# ESP32_DSP.net
KiCad netlist of a schematic drawn in EAGLE
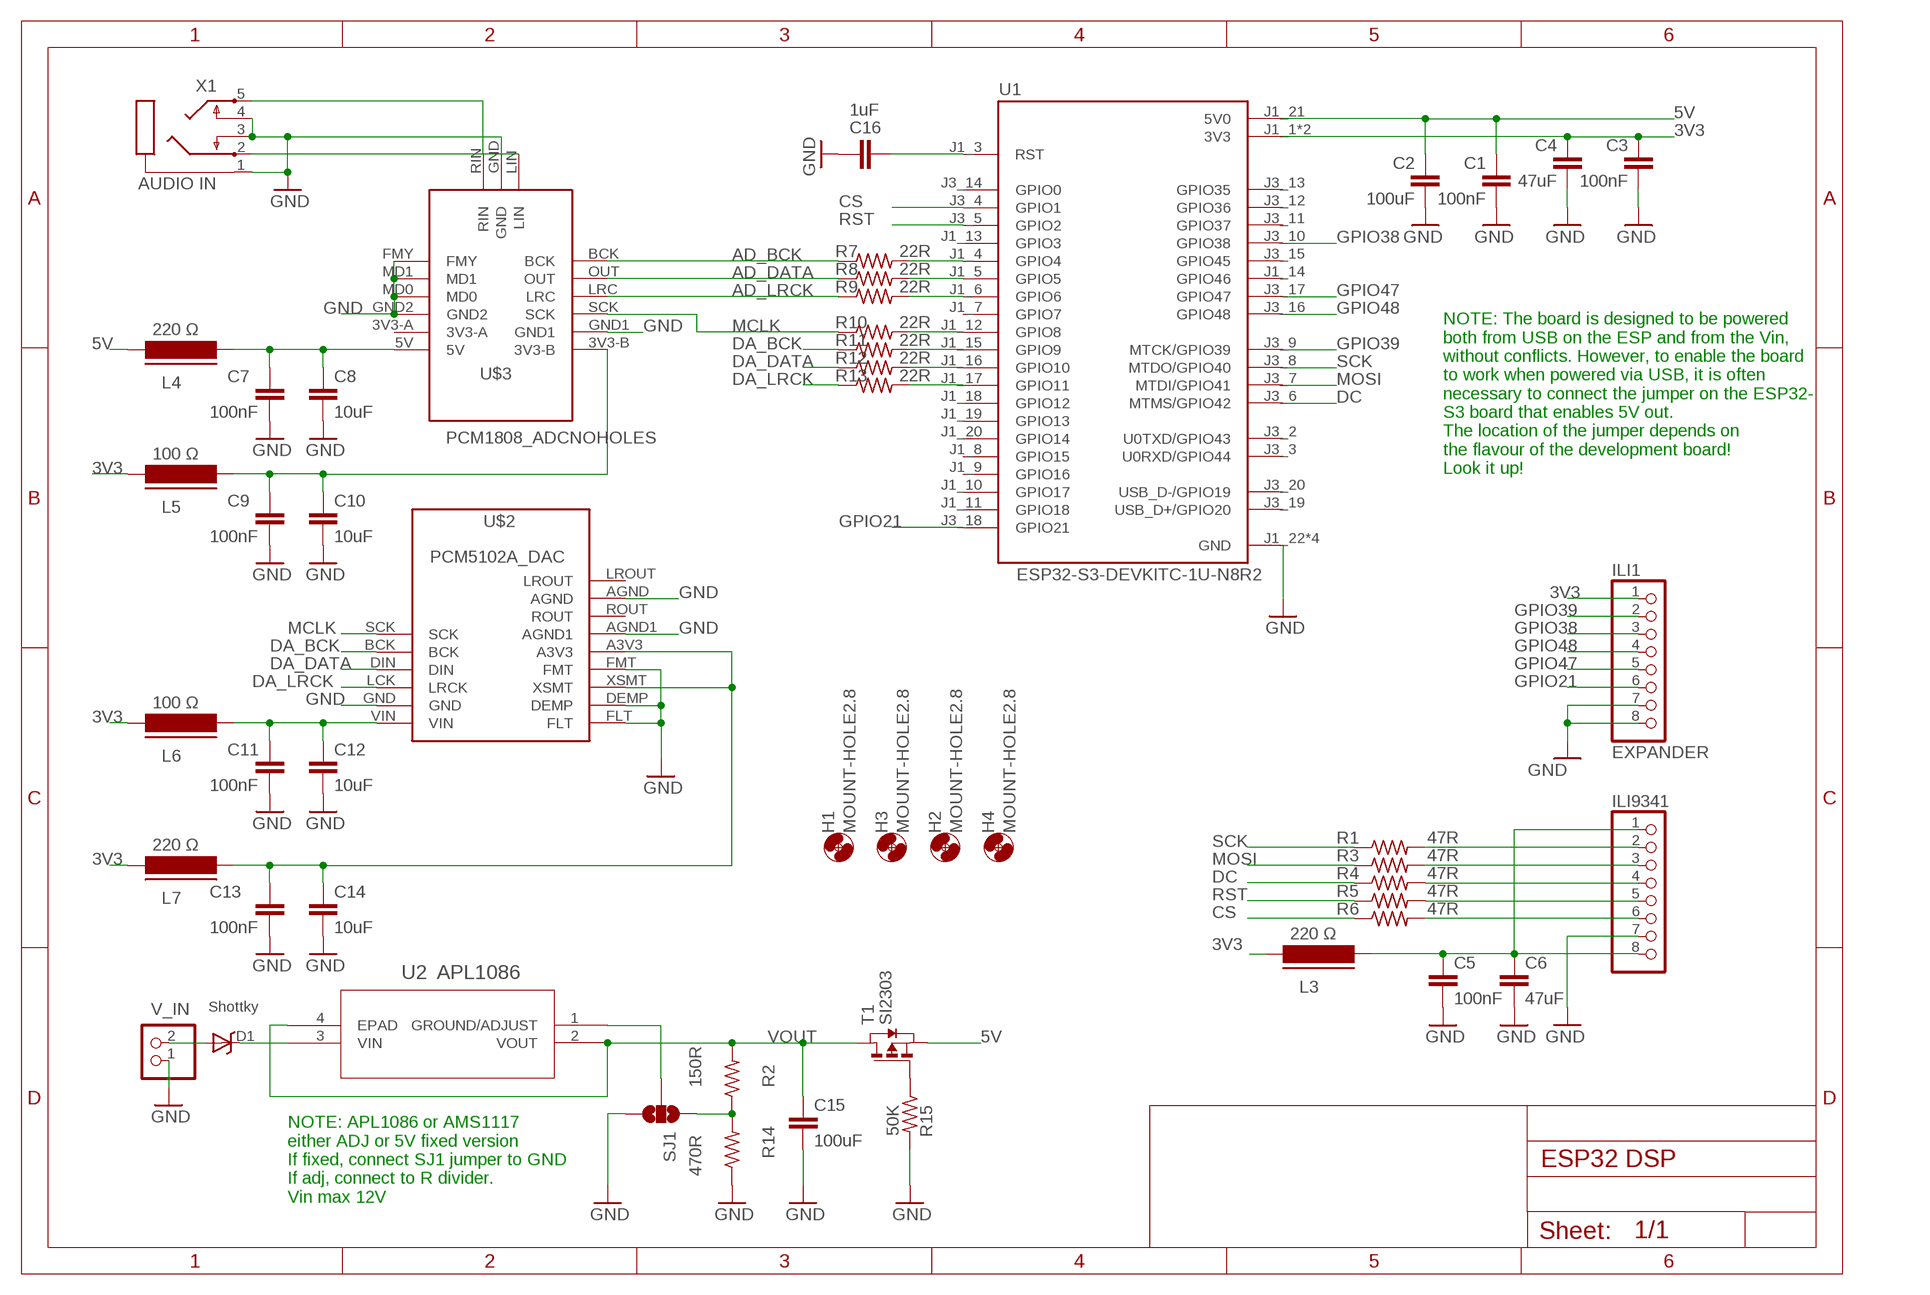
[diagram p0: schematic, sheet 1]

(export (version "E")
  (design (tool "Eeschema 10.0.6"))
  (components
    (comp (ref "C1")
      (value "100nF")
      (footprint "eagle-import:C0805")
      (libsource (lib "eagle-import") (part "C-EUC0805"))
    )
    (comp (ref "C2")
      (value "100uF")
      (footprint "eagle-import:C0805")
      (libsource (lib "eagle-import") (part "C-EUC0805"))
    )
    (comp (ref "C3")
      (value "100nF")
      (footprint "eagle-import:C0805")
      (libsource (lib "eagle-import") (part "C-EUC0805"))
    )
    (comp (ref "C4")
      (value "47uF")
      (footprint "eagle-import:C0805")
      (libsource (lib "eagle-import") (part "C-EUC0805"))
    )
    (comp (ref "C5")
      (value "100nF")
      (footprint "eagle-import:C0805")
      (libsource (lib "eagle-import") (part "C-EUC0805"))
    )
    (comp (ref "C6")
      (value "47uF")
      (footprint "eagle-import:C0805")
      (libsource (lib "eagle-import") (part "C-EUC0805"))
    )
    (comp (ref "C7")
      (value "100nF")
      (footprint "eagle-import:C0805")
      (libsource (lib "eagle-import") (part "C-EUC0805"))
    )
    (comp (ref "C8")
      (value "10uF")
      (footprint "eagle-import:C0805")
      (libsource (lib "eagle-import") (part "C-EUC0805"))
    )
    (comp (ref "C9")
      (value "100nF")
      (footprint "eagle-import:C0805")
      (libsource (lib "eagle-import") (part "C-EUC0805"))
    )
    (comp (ref "C10")
      (value "10uF")
      (footprint "eagle-import:C0805")
      (libsource (lib "eagle-import") (part "C-EUC0805"))
    )
    (comp (ref "C11")
      (value "100nF")
      (footprint "eagle-import:C0805")
      (libsource (lib "eagle-import") (part "C-EUC0805"))
    )
    (comp (ref "C12")
      (value "10uF")
      (footprint "eagle-import:C0805")
      (libsource (lib "eagle-import") (part "C-EUC0805"))
    )
    (comp (ref "C13")
      (value "100nF")
      (footprint "eagle-import:C0805")
      (libsource (lib "eagle-import") (part "C-EUC0805"))
    )
    (comp (ref "C14")
      (value "10uF")
      (footprint "eagle-import:C0805")
      (libsource (lib "eagle-import") (part "C-EUC0805"))
    )
    (comp (ref "C15")
      (value "100uF")
      (footprint "eagle-import:C0805")
      (libsource (lib "eagle-import") (part "C-EUC0805"))
    )
    (comp (ref "C16")
      (value "1uF")
      (footprint "eagle-import:C0805")
      (libsource (lib "eagle-import") (part "C-EUC0805"))
    )
    (comp (ref "D1")
      (value "Shottky")
      (footprint "eagle-import:SMA-403D")
      (libsource (lib "eagle-import") (part "DIODE-SCHOTTKYSMA-403D"))
    )
    (comp (ref "H1")
      (value "MOUNT-HOLE2.8")
      (footprint "eagle-import:2,8")
      (libsource (lib "eagle-import") (part "MOUNT-HOLE2.8"))
    )
    (comp (ref "H2")
      (value "MOUNT-HOLE2.8")
      (footprint "eagle-import:2,8")
      (libsource (lib "eagle-import") (part "MOUNT-HOLE2.8"))
    )
    (comp (ref "H3")
      (value "MOUNT-HOLE2.8")
      (footprint "eagle-import:2,8")
      (libsource (lib "eagle-import") (part "MOUNT-HOLE2.8"))
    )
    (comp (ref "H4")
      (value "MOUNT-HOLE2.8")
      (footprint "eagle-import:2,8")
      (libsource (lib "eagle-import") (part "MOUNT-HOLE2.8"))
    )
    (comp (ref "ILI1")
      (value "EXPANDER")
      (footprint "eagle-import:1X08")
      (libsource (lib "eagle-import") (part "PINHD-1X8"))
    )
    (comp (ref "ILI9341")
      (value "PINHD-1X8")
      (footprint "eagle-import:1X08")
      (libsource (lib "eagle-import") (part "PINHD-1X8"))
    )
    (comp (ref "L3")
      (value "220 Ω")
      (footprint "eagle-import:FB805")
      (libsource (lib "eagle-import") (part "FERRITE-0805"))
    )
    (comp (ref "L4")
      (value "220 Ω")
      (footprint "eagle-import:FB805")
      (libsource (lib "eagle-import") (part "FERRITE-0805"))
    )
    (comp (ref "L5")
      (value "100 Ω")
      (footprint "eagle-import:FB805")
      (libsource (lib "eagle-import") (part "FERRITE-0805"))
    )
    (comp (ref "L6")
      (value "100 Ω")
      (footprint "eagle-import:FB805")
      (libsource (lib "eagle-import") (part "FERRITE-0805"))
    )
    (comp (ref "L7")
      (value "220 Ω")
      (footprint "eagle-import:FB805")
      (libsource (lib "eagle-import") (part "FERRITE-0805"))
    )
    (comp (ref "R1")
      (value "47R")
      (footprint "eagle-import:M0805")
      (libsource (lib "eagle-import") (part "R-US_M0805"))
    )
    (comp (ref "R2")
      (value "150R")
      (footprint "eagle-import:M0805")
      (libsource (lib "eagle-import") (part "R-US_M0805"))
    )
    (comp (ref "R3")
      (value "47R")
      (footprint "eagle-import:M0805")
      (libsource (lib "eagle-import") (part "R-US_M0805"))
    )
    (comp (ref "R4")
      (value "47R")
      (footprint "eagle-import:M0805")
      (libsource (lib "eagle-import") (part "R-US_M0805"))
    )
    (comp (ref "R5")
      (value "47R")
      (footprint "eagle-import:M0805")
      (libsource (lib "eagle-import") (part "R-US_M0805"))
    )
    (comp (ref "R6")
      (value "47R")
      (footprint "eagle-import:M0805")
      (libsource (lib "eagle-import") (part "R-US_M0805"))
    )
    (comp (ref "R7")
      (value "22R")
      (footprint "eagle-import:M0805")
      (libsource (lib "eagle-import") (part "R-US_M0805"))
    )
    (comp (ref "R8")
      (value "22R")
      (footprint "eagle-import:M0805")
      (libsource (lib "eagle-import") (part "R-US_M0805"))
    )
    (comp (ref "R9")
      (value "22R")
      (footprint "eagle-import:M0805")
      (libsource (lib "eagle-import") (part "R-US_M0805"))
    )
    (comp (ref "R10")
      (value "22R")
      (footprint "eagle-import:M0805")
      (libsource (lib "eagle-import") (part "R-US_M0805"))
    )
    (comp (ref "R11")
      (value "22R")
      (footprint "eagle-import:M0805")
      (libsource (lib "eagle-import") (part "R-US_M0805"))
    )
    (comp (ref "R12")
      (value "22R")
      (footprint "eagle-import:M0805")
      (libsource (lib "eagle-import") (part "R-US_M0805"))
    )
    (comp (ref "R13")
      (value "22R")
      (footprint "eagle-import:M0805")
      (libsource (lib "eagle-import") (part "R-US_M0805"))
    )
    (comp (ref "R14")
      (value "470R")
      (footprint "eagle-import:M0805")
      (libsource (lib "eagle-import") (part "R-US_M0805"))
    )
    (comp (ref "R15")
      (value "50K")
      (footprint "eagle-import:M0805")
      (libsource (lib "eagle-import") (part "R-US_M0805"))
    )
    (comp (ref "SJ1")
      (value "SOLDERJUMPER_2WAYS")
      (footprint "eagle-import:SJ_3")
      (libsource (lib "eagle-import") (part "SOLDERJUMPER_2WAYS"))
    )
    (comp (ref "T1")
      (value "SI2303")
      (footprint "eagle-import:SOT-23")
      (libsource (lib "eagle-import") (part "PMOSSOT23"))
    )
    (comp (ref "U$2")
      (value "PCM5102A_DAC")
      (footprint "eagle-import:I2S_PCM_5100_SOUNDCARD")
      (libsource (lib "eagle-import") (part "PCM5102A_DAC"))
    )
    (comp (ref "U$3")
      (value "PCM1808_ADCNOHOLES")
      (footprint "eagle-import:CMJCU-1808-NOHOLES")
      (libsource (lib "eagle-import") (part "PCM1808_ADCNOHOLES"))
    )
    (comp (ref "U1")
      (value "ESP32-S3-DEVKITC-1U-N8R2")
      (footprint "eagle-import:XCVR_ESP32-S3-DEVKITC-1U-N8R2")
      (fields (field (name "MF") "Espressif Systems"))
      (libsource (lib "eagle-import") (part "ESP32-S3-DEVKITC-1U-N8R2"))
    )
    (comp (ref "U2")
      (value "APL1086")
      (footprint "eagle-import:SOT_AMS_ADS")
      (fields
        (field (name "MANUFACTURER_PART_NUMBER") "AMS1117-3.3")
        (field (name "COPYRIGHT") "Copyright (C) 2025 Ultra Librarian. All rights reserved.")
      )
      (libsource (lib "eagle-import") (part "APL1086"))
    )
    (comp (ref "V_IN")
      (value "5V")
      (footprint "eagle-import:1X02")
      (libsource (lib "eagle-import") (part "PINHD-1X2"))
    )
    (comp (ref "X1")
      (value "AUDIO IN")
      (footprint "eagle-import:STX3100")
      (libsource (lib "eagle-import") (part "STEREOJACK"))
    )
  )
  (nets
    (net (code "1") (name "/3V3") (class "Default")
      (node (ref "C3") (pin "1") (pinfunction "1_1") (pintype "passive"))
      (node (ref "C4") (pin "1") (pinfunction "1_1") (pintype "passive"))
      (node (ref "ILI1") (pin "1") (pinfunction "1_1") (pintype "passive"))
      (node (ref "L3") (pin "1") (pinfunction "1_1") (pintype "passive"))
      (node (ref "L5") (pin "1") (pinfunction "1_1") (pintype "passive"))
      (node (ref "L6") (pin "1") (pinfunction "1_1") (pintype "passive"))
      (node (ref "L7") (pin "1") (pinfunction "1_1") (pintype "passive"))
      (node (ref "U1") (pin "J1_1") (pinfunction "3V3_J1_1") (pintype "power_in"))
      (node (ref "U1") (pin "J1_2") (pinfunction "3V3_J1_2") (pintype "power_in"))
    )
    (net (code "2") (name "/5V") (class "Default")
      (node (ref "C1") (pin "1") (pinfunction "1_1") (pintype "passive"))
      (node (ref "C2") (pin "1") (pinfunction "1_1") (pintype "passive"))
      (node (ref "L4") (pin "1") (pinfunction "1_1") (pintype "passive"))
      (node (ref "T1") (pin "2") (pinfunction "S_2") (pintype "passive"))
      (node (ref "U1") (pin "J1_21") (pinfunction "5V0_J1_21") (pintype "power_in"))
    )
    (net (code "3") (name "/AD_BCK") (class "Default")
      (node (ref "R7") (pin "1") (pinfunction "1_1") (pintype "passive"))
      (node (ref "U$3") (pin "BCK") (pinfunction "BCK_BCK") (pintype "bidirectional"))
    )
    (net (code "4") (name "/AD_DATA") (class "Default")
      (node (ref "R8") (pin "1") (pinfunction "1_1") (pintype "passive"))
      (node (ref "U$3") (pin "OUT") (pinfunction "OUT_OUT") (pintype "bidirectional"))
    )
    (net (code "5") (name "/AD_LRCK") (class "Default")
      (node (ref "R9") (pin "1") (pinfunction "1_1") (pintype "passive"))
      (node (ref "U$3") (pin "LRC") (pinfunction "LRC_LRC") (pintype "bidirectional"))
    )
    (net (code "6") (name "/CS") (class "Default")
      (node (ref "R6") (pin "1") (pinfunction "1_1") (pintype "passive"))
      (node (ref "U1") (pin "J3_4") (pinfunction "GPIO1_J3_4") (pintype "bidirectional"))
    )
    (net (code "7") (name "/DA_BCK") (class "Default")
      (node (ref "R11") (pin "1") (pinfunction "1_1") (pintype "passive"))
      (node (ref "U$2") (pin "BCK") (pinfunction "BCK_BCK") (pintype "bidirectional"))
    )
    (net (code "8") (name "/DA_DATA") (class "Default")
      (node (ref "R12") (pin "1") (pinfunction "1_1") (pintype "passive"))
      (node (ref "U$2") (pin "DIN") (pinfunction "DIN_DIN") (pintype "bidirectional"))
    )
    (net (code "9") (name "/DA_LRCK") (class "Default")
      (node (ref "R13") (pin "1") (pinfunction "1_1") (pintype "passive"))
      (node (ref "U$2") (pin "LCK") (pinfunction "LRCK_LCK") (pintype "bidirectional"))
    )
    (net (code "10") (name "/DC") (class "Default")
      (node (ref "R4") (pin "1") (pinfunction "1_1") (pintype "passive"))
      (node (ref "U1") (pin "J3_6") (pinfunction "MTMS/GPIO42_J3_6") (pintype "bidirectional"))
    )
    (net (code "11") (name "/GPIO21") (class "Default")
      (node (ref "ILI1") (pin "6") (pinfunction "6_6") (pintype "passive"))
      (node (ref "U1") (pin "J3_18") (pinfunction "GPIO21_J3_18") (pintype "bidirectional"))
    )
    (net (code "12") (name "/GPIO38") (class "Default")
      (node (ref "ILI1") (pin "3") (pinfunction "3_3") (pintype "passive"))
      (node (ref "U1") (pin "J3_10") (pinfunction "GPIO38_J3_10") (pintype "bidirectional"))
    )
    (net (code "13") (name "/GPIO39") (class "Default")
      (node (ref "ILI1") (pin "2") (pinfunction "2_2") (pintype "passive"))
      (node (ref "U1") (pin "J3_9") (pinfunction "MTCK/GPIO39_J3_9") (pintype "bidirectional"))
    )
    (net (code "14") (name "/GPIO47") (class "Default")
      (node (ref "ILI1") (pin "5") (pinfunction "5_5") (pintype "passive"))
      (node (ref "U1") (pin "J3_17") (pinfunction "GPIO47_J3_17") (pintype "bidirectional"))
    )
    (net (code "15") (name "/GPIO48") (class "Default")
      (node (ref "ILI1") (pin "4") (pinfunction "4_4") (pintype "passive"))
      (node (ref "U1") (pin "J3_16") (pinfunction "GPIO48_J3_16") (pintype "bidirectional"))
    )
    (net (code "16") (name "/MCLK") (class "Default")
      (node (ref "R10") (pin "1") (pinfunction "1_1") (pintype "passive"))
      (node (ref "U$2") (pin "SCK") (pinfunction "SCK_SCK") (pintype "bidirectional"))
      (node (ref "U$3") (pin "SCK") (pinfunction "SCK_SCK") (pintype "bidirectional"))
    )
    (net (code "17") (name "/MOSI") (class "Default")
      (node (ref "R3") (pin "1") (pinfunction "1_1") (pintype "passive"))
      (node (ref "U1") (pin "J3_7") (pinfunction "MTDI/GPIO41_J3_7") (pintype "bidirectional"))
    )
    (net (code "18") (name "/RST") (class "Default")
      (node (ref "R5") (pin "1") (pinfunction "1_1") (pintype "passive"))
      (node (ref "U1") (pin "J3_5") (pinfunction "GPIO2_J3_5") (pintype "bidirectional"))
    )
    (net (code "19") (name "/SCK") (class "Default")
      (node (ref "R1") (pin "1") (pinfunction "1_1") (pintype "passive"))
      (node (ref "U1") (pin "J3_8") (pinfunction "MTDO/GPIO40_J3_8") (pintype "bidirectional"))
    )
    (net (code "20") (name "/VOUT") (class "Default")
      (node (ref "C15") (pin "1") (pinfunction "1_1") (pintype "passive"))
      (node (ref "R2") (pin "2") (pinfunction "2_2") (pintype "passive"))
      (node (ref "T1") (pin "1") (pinfunction "D_1") (pintype "passive"))
      (node (ref "U2") (pin "2") (pinfunction "VOUT_2") (pintype "output"))
      (node (ref "U2") (pin "4") (pinfunction "EPAD_4") (pintype "power_in"))
    )
    (net (code "21") (name "GND") (class "Default")
      (node (ref "C1") (pin "2") (pinfunction "2_2") (pintype "passive"))
      (node (ref "C10") (pin "2") (pinfunction "2_2") (pintype "passive"))
      (node (ref "C11") (pin "2") (pinfunction "2_2") (pintype "passive"))
      (node (ref "C12") (pin "2") (pinfunction "2_2") (pintype "passive"))
      (node (ref "C13") (pin "2") (pinfunction "2_2") (pintype "passive"))
      (node (ref "C14") (pin "2") (pinfunction "2_2") (pintype "passive"))
      (node (ref "C15") (pin "2") (pinfunction "2_2") (pintype "passive"))
      (node (ref "C16") (pin "2") (pinfunction "2_2") (pintype "passive"))
      (node (ref "C2") (pin "2") (pinfunction "2_2") (pintype "passive"))
      (node (ref "C3") (pin "2") (pinfunction "2_2") (pintype "passive"))
      (node (ref "C4") (pin "2") (pinfunction "2_2") (pintype "passive"))
      (node (ref "C5") (pin "2") (pinfunction "2_2") (pintype "passive"))
      (node (ref "C6") (pin "2") (pinfunction "2_2") (pintype "passive"))
      (node (ref "C7") (pin "2") (pinfunction "2_2") (pintype "passive"))
      (node (ref "C8") (pin "2") (pinfunction "2_2") (pintype "passive"))
      (node (ref "C9") (pin "2") (pinfunction "2_2") (pintype "passive"))
      (node (ref "ILI1") (pin "7") (pinfunction "7_7") (pintype "passive"))
      (node (ref "ILI1") (pin "8") (pinfunction "8_8") (pintype "passive"))
      (node (ref "ILI9341") (pin "7") (pinfunction "7_7") (pintype "passive"))
      (node (ref "R14") (pin "1") (pinfunction "1_1") (pintype "passive"))
      (node (ref "R15") (pin "2") (pinfunction "2_2") (pintype "passive"))
      (node (ref "SJ1") (pin "3") (pinfunction "3_3") (pintype "passive"))
      (node (ref "U$2") (pin "AGND") (pinfunction "AGND_AGND") (pintype "bidirectional"))
      (node (ref "U$2") (pin "AGND1") (pinfunction "AGND1_AGND1") (pintype "bidirectional"))
      (node (ref "U$2") (pin "DEMP") (pinfunction "DEMP_DEMP") (pintype "bidirectional"))
      (node (ref "U$2") (pin "FLT") (pinfunction "FLT_FLT") (pintype "bidirectional"))
      (node (ref "U$2") (pin "FMT") (pinfunction "FMT_FMT") (pintype "bidirectional"))
      (node (ref "U$2") (pin "GND") (pinfunction "GND_GND") (pintype "bidirectional"))
      (node (ref "U$3") (pin "FMY") (pinfunction "FMY_FMY") (pintype "bidirectional"))
      (node (ref "U$3") (pin "GND") (pinfunction "GND_GND") (pintype "bidirectional"))
      (node (ref "U$3") (pin "GND1") (pinfunction "GND1_GND1") (pintype "bidirectional"))
      (node (ref "U$3") (pin "GND2") (pinfunction "GND2_GND2") (pintype "bidirectional"))
      (node (ref "U$3") (pin "MD0") (pinfunction "MD0_MD0") (pintype "bidirectional"))
      (node (ref "U$3") (pin "MD1") (pinfunction "MD1_MD1") (pintype "bidirectional"))
      (node (ref "U1") (pin "J1_22") (pinfunction "GND_J1_22") (pintype "power_in"))
      (node (ref "U1") (pin "J3_1") (pinfunction "GND_J3_1") (pintype "power_in"))
      (node (ref "U1") (pin "J3_21") (pinfunction "GND_J3_21") (pintype "power_in"))
      (node (ref "U1") (pin "J3_22") (pinfunction "GND_J3_22") (pintype "power_in"))
      (node (ref "V_IN") (pin "1") (pinfunction "1_1") (pintype "passive"))
      (node (ref "X1") (pin "1") (pinfunction "1_1") (pintype "passive"))
      (node (ref "X1") (pin "3") (pinfunction "3_3") (pintype "passive"))
      (node (ref "X1") (pin "4") (pinfunction "4_4") (pintype "passive"))
    )
    (net (code "22") (name "Net-(C5-Pad1)") (class "Default")
      (node (ref "C5") (pin "1") (pinfunction "1_1") (pintype "passive"))
      (node (ref "C6") (pin "1") (pinfunction "1_1") (pintype "passive"))
      (node (ref "ILI9341") (pin "1") (pinfunction "1_1") (pintype "passive"))
      (node (ref "ILI9341") (pin "8") (pinfunction "8_8") (pintype "passive"))
      (node (ref "L3") (pin "2") (pinfunction "2_2") (pintype "passive"))
    )
    (net (code "23") (name "Net-(C7-Pad1)") (class "Default")
      (node (ref "C7") (pin "1") (pinfunction "1_1") (pintype "passive"))
      (node (ref "C8") (pin "1") (pinfunction "1_1") (pintype "passive"))
      (node (ref "L4") (pin "2") (pinfunction "2_2") (pintype "passive"))
      (node (ref "U$3") (pin "5V") (pinfunction "5V_5V") (pintype "bidirectional"))
    )
    (net (code "24") (name "Net-(C10-Pad1)") (class "Default")
      (node (ref "C10") (pin "1") (pinfunction "1_1") (pintype "passive"))
      (node (ref "C9") (pin "1") (pinfunction "1_1") (pintype "passive"))
      (node (ref "L5") (pin "2") (pinfunction "2_2") (pintype "passive"))
      (node (ref "U$3") (pin "3V3-B") (pinfunction "3V3-B_3V3-B") (pintype "bidirectional"))
    )
    (net (code "25") (name "Net-(C11-Pad1)") (class "Default")
      (node (ref "C11") (pin "1") (pinfunction "1_1") (pintype "passive"))
      (node (ref "C12") (pin "1") (pinfunction "1_1") (pintype "passive"))
      (node (ref "L6") (pin "2") (pinfunction "2_2") (pintype "passive"))
      (node (ref "U$2") (pin "VIN") (pinfunction "VIN_VIN") (pintype "bidirectional"))
    )
    (net (code "26") (name "Net-(C13-Pad1)") (class "Default")
      (node (ref "C13") (pin "1") (pinfunction "1_1") (pintype "passive"))
      (node (ref "C14") (pin "1") (pinfunction "1_1") (pintype "passive"))
      (node (ref "L7") (pin "2") (pinfunction "2_2") (pintype "passive"))
      (node (ref "U$2") (pin "A3V3") (pinfunction "A3V3_A3V3") (pintype "bidirectional"))
      (node (ref "U$2") (pin "XSMT") (pinfunction "XSMT_XSMT") (pintype "bidirectional"))
    )
    (net (code "27") (name "Net-(D1-PadA)") (class "Default")
      (node (ref "D1") (pin "A") (pinfunction "A_A") (pintype "passive"))
      (node (ref "V_IN") (pin "2") (pinfunction "2_2") (pintype "passive"))
    )
    (net (code "28") (name "Net-(ILI9341-Pad2)") (class "Default")
      (node (ref "ILI9341") (pin "2") (pinfunction "2_2") (pintype "passive"))
      (node (ref "R1") (pin "2") (pinfunction "2_2") (pintype "passive"))
    )
    (net (code "29") (name "Net-(ILI9341-Pad3)") (class "Default")
      (node (ref "ILI9341") (pin "3") (pinfunction "3_3") (pintype "passive"))
      (node (ref "R3") (pin "2") (pinfunction "2_2") (pintype "passive"))
    )
    (net (code "30") (name "Net-(ILI9341-Pad4)") (class "Default")
      (node (ref "ILI9341") (pin "4") (pinfunction "4_4") (pintype "passive"))
      (node (ref "R4") (pin "2") (pinfunction "2_2") (pintype "passive"))
    )
    (net (code "31") (name "Net-(ILI9341-Pad5)") (class "Default")
      (node (ref "ILI9341") (pin "5") (pinfunction "5_5") (pintype "passive"))
      (node (ref "R5") (pin "2") (pinfunction "2_2") (pintype "passive"))
    )
    (net (code "32") (name "Net-(ILI9341-Pad6)") (class "Default")
      (node (ref "ILI9341") (pin "6") (pinfunction "6_6") (pintype "passive"))
      (node (ref "R6") (pin "2") (pinfunction "2_2") (pintype "passive"))
    )
    (net (code "33") (name "Net-(R14-Pad2)") (class "Default")
      (node (ref "R14") (pin "2") (pinfunction "2_2") (pintype "passive"))
      (node (ref "R2") (pin "1") (pinfunction "1_1") (pintype "passive"))
      (node (ref "SJ1") (pin "1") (pinfunction "1_1") (pintype "passive"))
    )
    (net (code "34") (name "Net-(T1-G)") (class "Default")
      (node (ref "R15") (pin "1") (pinfunction "1_1") (pintype "passive"))
      (node (ref "T1") (pin "3") (pinfunction "G_3") (pintype "passive"))
    )
    (net (code "35") (name "Net-(U$3-PadLIN)") (class "Default")
      (node (ref "U$3") (pin "LIN") (pinfunction "LIN_LIN") (pintype "bidirectional"))
      (node (ref "X1") (pin "2") (pinfunction "2_2") (pintype "passive"))
    )
    (net (code "36") (name "Net-(U$3-PadRIN)") (class "Default")
      (node (ref "U$3") (pin "RIN") (pinfunction "RIN_RIN") (pintype "bidirectional"))
      (node (ref "X1") (pin "5") (pinfunction "5_5") (pintype "passive"))
    )
    (net (code "37") (name "Net-(U1-GPIO4)") (class "Default")
      (node (ref "R7") (pin "2") (pinfunction "2_2") (pintype "passive"))
      (node (ref "U1") (pin "J1_4") (pinfunction "GPIO4_J1_4") (pintype "bidirectional"))
    )
    (net (code "38") (name "Net-(U1-GPIO5)") (class "Default")
      (node (ref "R8") (pin "2") (pinfunction "2_2") (pintype "passive"))
      (node (ref "U1") (pin "J1_5") (pinfunction "GPIO5_J1_5") (pintype "bidirectional"))
    )
    (net (code "39") (name "Net-(U1-GPIO6)") (class "Default")
      (node (ref "R9") (pin "2") (pinfunction "2_2") (pintype "passive"))
      (node (ref "U1") (pin "J1_6") (pinfunction "GPIO6_J1_6") (pintype "bidirectional"))
    )
    (net (code "40") (name "Net-(U1-GPIO8)") (class "Default")
      (node (ref "R10") (pin "2") (pinfunction "2_2") (pintype "passive"))
      (node (ref "U1") (pin "J1_12") (pinfunction "GPIO8_J1_12") (pintype "bidirectional"))
    )
    (net (code "41") (name "Net-(U1-GPIO9)") (class "Default")
      (node (ref "R11") (pin "2") (pinfunction "2_2") (pintype "passive"))
      (node (ref "U1") (pin "J1_15") (pinfunction "GPIO9_J1_15") (pintype "bidirectional"))
    )
    (net (code "42") (name "Net-(U1-GPIO10)") (class "Default")
      (node (ref "R12") (pin "2") (pinfunction "2_2") (pintype "passive"))
      (node (ref "U1") (pin "J1_16") (pinfunction "GPIO10_J1_16") (pintype "bidirectional"))
    )
    (net (code "43") (name "Net-(U1-GPIO11)") (class "Default")
      (node (ref "R13") (pin "2") (pinfunction "2_2") (pintype "passive"))
      (node (ref "U1") (pin "J1_17") (pinfunction "GPIO11_J1_17") (pintype "bidirectional"))
    )
    (net (code "44") (name "Net-(U1-RST)") (class "Default")
      (node (ref "C16") (pin "1") (pinfunction "1_1") (pintype "passive"))
      (node (ref "U1") (pin "J1_3") (pinfunction "RST_J1_3") (pintype "input"))
    )
    (net (code "45") (name "Net-(U2-GROUND{slash}ADJUST)") (class "Default")
      (node (ref "SJ1") (pin "2") (pinfunction "2_2") (pintype "passive"))
      (node (ref "U2") (pin "1") (pinfunction "GROUND/ADJUST_1") (pintype "passive"))
    )
    (net (code "46") (name "Net-(U2-VIN)") (class "Default")
      (node (ref "D1") (pin "C") (pinfunction "C_C") (pintype "passive"))
      (node (ref "U2") (pin "3") (pinfunction "VIN_3") (pintype "input"))
    )
    (net (code "47") (name "unconnected-(U$2-PadLROUT)") (class "Default")
      (node (ref "U$2") (pin "LROUT") (pinfunction "LROUT_LROUT") (pintype "bidirectional"))
    )
    (net (code "48") (name "unconnected-(U$2-PadROUT)") (class "Default")
      (node (ref "U$2") (pin "ROUT") (pinfunction "ROUT_ROUT") (pintype "bidirectional"))
    )
    (net (code "49") (name "unconnected-(U$3-Pad3V3-A)") (class "Default")
      (node (ref "U$3") (pin "3V3-A") (pinfunction "3V3-A_3V3-A") (pintype "bidirectional"))
    )
    (net (code "50") (name "unconnected-(U1-GPIO0-PadJ3_14)") (class "Default")
      (node (ref "U1") (pin "J3_14") (pinfunction "GPIO0_J3_14") (pintype "bidirectional"))
    )
    (net (code "51") (name "unconnected-(U1-GPIO3-PadJ1_13)") (class "Default")
      (node (ref "U1") (pin "J1_13") (pinfunction "GPIO3_J1_13") (pintype "bidirectional"))
    )
    (net (code "52") (name "unconnected-(U1-GPIO7-PadJ1_7)") (class "Default")
      (node (ref "U1") (pin "J1_7") (pinfunction "GPIO7_J1_7") (pintype "bidirectional"))
    )
    (net (code "53") (name "unconnected-(U1-GPIO12-PadJ1_18)") (class "Default")
      (node (ref "U1") (pin "J1_18") (pinfunction "GPIO12_J1_18") (pintype "bidirectional"))
    )
    (net (code "54") (name "unconnected-(U1-GPIO13-PadJ1_19)") (class "Default")
      (node (ref "U1") (pin "J1_19") (pinfunction "GPIO13_J1_19") (pintype "bidirectional"))
    )
    (net (code "55") (name "unconnected-(U1-GPIO14-PadJ1_20)") (class "Default")
      (node (ref "U1") (pin "J1_20") (pinfunction "GPIO14_J1_20") (pintype "bidirectional"))
    )
    (net (code "56") (name "unconnected-(U1-GPIO15-PadJ1_8)") (class "Default")
      (node (ref "U1") (pin "J1_8") (pinfunction "GPIO15_J1_8") (pintype "bidirectional"))
    )
    (net (code "57") (name "unconnected-(U1-GPIO16-PadJ1_9)") (class "Default")
      (node (ref "U1") (pin "J1_9") (pinfunction "GPIO16_J1_9") (pintype "bidirectional"))
    )
    (net (code "58") (name "unconnected-(U1-GPIO17-PadJ1_10)") (class "Default")
      (node (ref "U1") (pin "J1_10") (pinfunction "GPIO17_J1_10") (pintype "bidirectional"))
    )
    (net (code "59") (name "unconnected-(U1-GPIO18-PadJ1_11)") (class "Default")
      (node (ref "U1") (pin "J1_11") (pinfunction "GPIO18_J1_11") (pintype "bidirectional"))
    )
    (net (code "60") (name "unconnected-(U1-GPIO35-PadJ3_13)") (class "Default")
      (node (ref "U1") (pin "J3_13") (pinfunction "GPIO35_J3_13") (pintype "bidirectional"))
    )
    (net (code "61") (name "unconnected-(U1-GPIO36-PadJ3_12)") (class "Default")
      (node (ref "U1") (pin "J3_12") (pinfunction "GPIO36_J3_12") (pintype "bidirectional"))
    )
    (net (code "62") (name "unconnected-(U1-GPIO37-PadJ3_11)") (class "Default")
      (node (ref "U1") (pin "J3_11") (pinfunction "GPIO37_J3_11") (pintype "bidirectional"))
    )
    (net (code "63") (name "unconnected-(U1-GPIO45-PadJ3_15)") (class "Default")
      (node (ref "U1") (pin "J3_15") (pinfunction "GPIO45_J3_15") (pintype "bidirectional"))
    )
    (net (code "64") (name "unconnected-(U1-GPIO46-PadJ1_14)") (class "Default")
      (node (ref "U1") (pin "J1_14") (pinfunction "GPIO46_J1_14") (pintype "bidirectional"))
    )
    (net (code "65") (name "unconnected-(U1-U0RXD{slash}GPIO44-PadJ3_3)") (class "Default")
      (node (ref "U1") (pin "J3_3") (pinfunction "U0RXD/GPIO44_J3_3") (pintype "bidirectional"))
    )
    (net (code "66") (name "unconnected-(U1-U0TXD{slash}GPIO43-PadJ3_2)") (class "Default")
      (node (ref "U1") (pin "J3_2") (pinfunction "U0TXD/GPIO43_J3_2") (pintype "bidirectional"))
    )
    (net (code "67") (name "unconnected-(U1-USB_D+{slash}GPIO20-PadJ3_19)") (class "Default")
      (node (ref "U1") (pin "J3_19") (pinfunction "USB_D+/GPIO20_J3_19") (pintype "bidirectional"))
    )
    (net (code "68") (name "unconnected-(U1-USB_D-{slash}GPIO19-PadJ3_20)") (class "Default")
      (node (ref "U1") (pin "J3_20") (pinfunction "USB_D-/GPIO19_J3_20") (pintype "bidirectional"))
    )
  )
)
